# mcu.net
KiCad netlist of a schematic drawn in Altium Designer
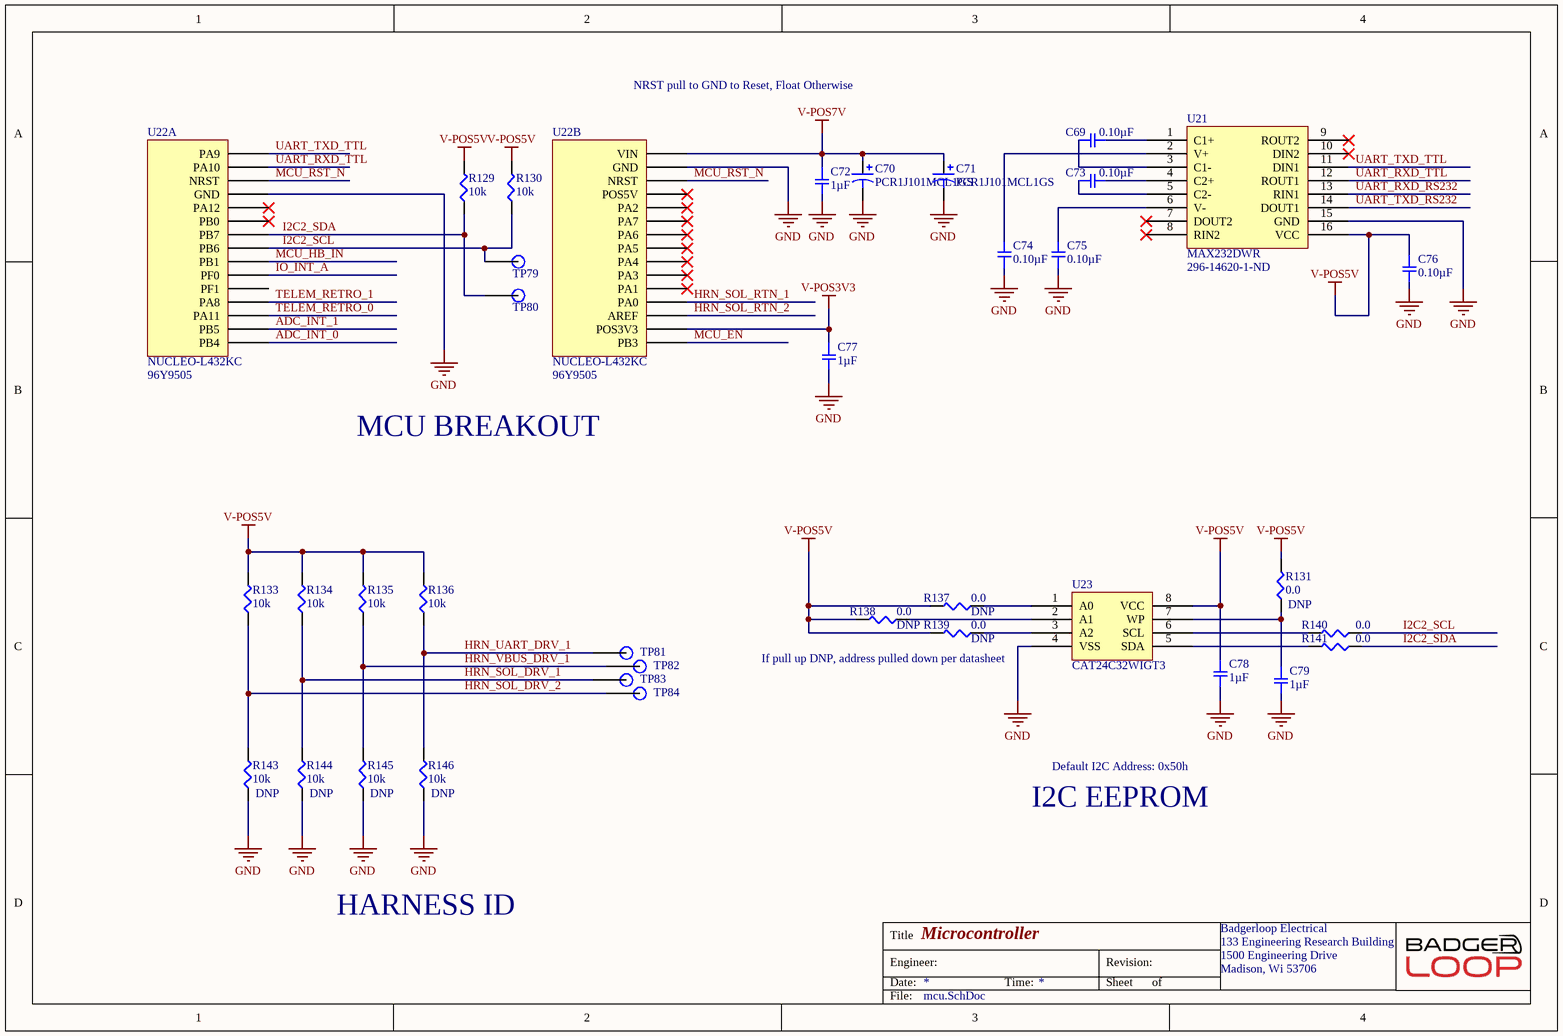
[diagram p0: mcu.SchDoc]

(export (version "E")
  (design (tool "Eeschema 10.0.6"))
  (components
    (comp (ref "C69")
      (value "0.10µF")
      (footprint "SMD-0805C")
      (description "CAP CER 0.1UF 16V X7R 0805")
      (fields
        (field (name "DIGI-KEY PART NUMBER") "490-12557-1-ND")
        (field (name "PART NUMBER") "GRM219R71C104JA01D")
      )
      (libsource (lib "capacitors") (part "GRM219R71C104JA01D"))
    )
    (comp (ref "C70")
      (value "PCR1J101MCL1GS")
      (footprint "CAPAE110103X126M")
      (description "CAP ALUM POLY 100UF 20% 63V SMD")
      (fields (field (name "MANUFACTURER") "Nichicon") (field (name "TOLERANCE") "20%"))
      (libsource (lib "capacitors") (part "PCR1J101MCL1GS"))
    )
    (comp (ref "C71")
      (value "PCR1J101MCL1GS")
      (footprint "CAPAE110103X126M")
      (description "CAP ALUM POLY 100UF 20% 63V SMD")
      (fields (field (name "MANUFACTURER") "Nichicon") (field (name "TOLERANCE") "20%"))
      (libsource (lib "capacitors") (part "PCR1J101MCL1GS"))
    )
    (comp (ref "C72")
      (value "1µF")
      (footprint "SMD-0805C")
      (description "CAP CER 1UF 50V X7R 0805")
      (fields
        (field (name "DIGI-KEY PART NUMBER") "490-4736-1-ND")
        (field (name "PART NUMBER") "GRM21BR71H105KA12L")
      )
      (libsource (lib "capacitors") (part "GRM21BR71H105KA12L"))
    )
    (comp (ref "C73")
      (value "0.10µF")
      (footprint "SMD-0805C")
      (description "CAP CER 0.1UF 16V X7R 0805")
      (fields
        (field (name "DIGI-KEY PART NUMBER") "490-12557-1-ND")
        (field (name "PART NUMBER") "GRM219R71C104JA01D")
      )
      (libsource (lib "capacitors") (part "GRM219R71C104JA01D"))
    )
    (comp (ref "C74")
      (value "0.10µF")
      (footprint "SMD-0805C")
      (description "CAP CER 0.1UF 16V X7R 0805")
      (fields
        (field (name "DIGI-KEY PART NUMBER") "490-12557-1-ND")
        (field (name "PART NUMBER") "GRM219R71C104JA01D")
      )
      (libsource (lib "capacitors") (part "GRM219R71C104JA01D"))
    )
    (comp (ref "C75")
      (value "0.10µF")
      (footprint "SMD-0805C")
      (description "CAP CER 0.1UF 16V X7R 0805")
      (fields
        (field (name "DIGI-KEY PART NUMBER") "490-12557-1-ND")
        (field (name "PART NUMBER") "GRM219R71C104JA01D")
      )
      (libsource (lib "capacitors") (part "GRM219R71C104JA01D"))
    )
    (comp (ref "C76")
      (value "0.10µF")
      (footprint "SMD-0805C")
      (description "CAP CER 0.1UF 25V X7R 0805")
      (fields
        (field (name "DIGI-KEY PART NUMBER") "490-12754-1-ND")
        (field (name "PART NUMBER") "GRM219R71E104KA01D")
      )
      (libsource (lib "capacitors") (part "GRM219R71E104KA01D"))
    )
    (comp (ref "C77")
      (value "1µF")
      (footprint "SMD-0805C")
      (description "CAP CER 1UF 50V X7R 0805")
      (fields
        (field (name "DIGI-KEY PART NUMBER") "490-4736-1-ND")
        (field (name "PART NUMBER") "GRM21BR71H105KA12L")
      )
      (libsource (lib "capacitors") (part "GRM21BR71H105KA12L"))
    )
    (comp (ref "C78")
      (value "1µF")
      (footprint "SMD-0805C")
      (description "CAP CER 1UF 50V X7R 0805")
      (fields
        (field (name "DIGI-KEY PART NUMBER") "490-4736-1-ND")
        (field (name "PART NUMBER") "GRM21BR71H105KA12L")
      )
      (libsource (lib "capacitors") (part "GRM21BR71H105KA12L"))
    )
    (comp (ref "C79")
      (value "1µF")
      (footprint "SMD-0805C")
      (description "CAP CER 1UF 50V X7R 0805")
      (fields
        (field (name "DIGI-KEY PART NUMBER") "490-4736-1-ND")
        (field (name "PART NUMBER") "GRM21BR71H105KA12L")
      )
      (libsource (lib "capacitors") (part "GRM21BR71H105KA12L"))
    )
    (comp (ref "R129")
      (value "10k")
      (footprint "SMD-0805-RES")
      (description "RES SMD 10K OHM 5% 1/2W 0805")
      (fields (field (name "PART NUMBER") "ERJ-P06J103V") (field (name "DIGI-KEY PART NUMBER") "P10KADCT-ND"))
      (libsource (lib "resistors") (part "ERJ-P06J103V"))
    )
    (comp (ref "R130")
      (value "10k")
      (footprint "SMD-0805-RES")
      (description "RES SMD 10K OHM 5% 1/2W 0805")
      (fields (field (name "PART NUMBER") "ERJ-P06J103V") (field (name "DIGI-KEY PART NUMBER") "P10KADCT-ND"))
      (libsource (lib "resistors") (part "ERJ-P06J103V"))
    )
    (comp (ref "R131")
      (value "0.0")
      (footprint "SMD-0805-RES")
      (description "RES SMD 0.0 OHM JUMPER 1/8W 0805")
      (fields
        (field (name "PART NUMBER") "ERJ-6GEY0R00V")
        (field (name "DIGI-KEY PART NUMBER") "P0.0ACT-ND")
        (field (name "DNP") "DNP")
      )
      (libsource (lib "resistors") (part "ERJ-6GEY0R00V"))
    )
    (comp (ref "R133")
      (value "10k")
      (footprint "SMD-0805-RES")
      (description "RES SMD 10K OHM 5% 1/2W 0805")
      (fields (field (name "PART NUMBER") "ERJ-P06J103V") (field (name "DIGI-KEY PART NUMBER") "P10KADCT-ND"))
      (libsource (lib "resistors") (part "ERJ-P06J103V"))
    )
    (comp (ref "R134")
      (value "10k")
      (footprint "SMD-0805-RES")
      (description "RES SMD 10K OHM 5% 1/2W 0805")
      (fields (field (name "PART NUMBER") "ERJ-P06J103V") (field (name "DIGI-KEY PART NUMBER") "P10KADCT-ND"))
      (libsource (lib "resistors") (part "ERJ-P06J103V"))
    )
    (comp (ref "R135")
      (value "10k")
      (footprint "SMD-0805-RES")
      (description "RES SMD 10K OHM 5% 1/2W 0805")
      (fields (field (name "PART NUMBER") "ERJ-P06J103V") (field (name "DIGI-KEY PART NUMBER") "P10KADCT-ND"))
      (libsource (lib "resistors") (part "ERJ-P06J103V"))
    )
    (comp (ref "R136")
      (value "10k")
      (footprint "SMD-0805-RES")
      (description "RES SMD 10K OHM 5% 1/2W 0805")
      (fields (field (name "PART NUMBER") "ERJ-P06J103V") (field (name "DIGI-KEY PART NUMBER") "P10KADCT-ND"))
      (libsource (lib "resistors") (part "ERJ-P06J103V"))
    )
    (comp (ref "R137")
      (value "0.0")
      (footprint "SMD-0805-RES")
      (description "RES SMD 0.0 OHM JUMPER 1/8W 0805")
      (fields
        (field (name "PART NUMBER") "ERJ-6GEY0R00V")
        (field (name "DIGI-KEY PART NUMBER") "P0.0ACT-ND")
        (field (name "DNP") "DNP")
      )
      (libsource (lib "resistors") (part "ERJ-6GEY0R00V"))
    )
    (comp (ref "R138")
      (value "0.0")
      (footprint "SMD-0805-RES")
      (description "RES SMD 0.0 OHM JUMPER 1/8W 0805")
      (fields
        (field (name "PART NUMBER") "ERJ-6GEY0R00V")
        (field (name "DIGI-KEY PART NUMBER") "P0.0ACT-ND")
        (field (name "DNP") "DNP")
      )
      (libsource (lib "resistors") (part "ERJ-6GEY0R00V"))
    )
    (comp (ref "R139")
      (value "0.0")
      (footprint "SMD-0805-RES")
      (description "RES SMD 0.0 OHM JUMPER 1/8W 0805")
      (fields
        (field (name "PART NUMBER") "ERJ-6GEY0R00V")
        (field (name "DIGI-KEY PART NUMBER") "P0.0ACT-ND")
        (field (name "DNP") "DNP")
      )
      (libsource (lib "resistors") (part "ERJ-6GEY0R00V"))
    )
    (comp (ref "R140")
      (value "0.0")
      (footprint "SMD-0805-RES")
      (description "RES SMD 0.0 OHM JUMPER 1/8W 0805")
      (fields (field (name "PART NUMBER") "ERJ-6GEY0R00V") (field (name "DIGI-KEY PART NUMBER") "P0.0ACT-ND"))
      (libsource (lib "resistors") (part "ERJ-6GEY0R00V"))
    )
    (comp (ref "R141")
      (value "0.0")
      (footprint "SMD-0805-RES")
      (description "RES SMD 0.0 OHM JUMPER 1/8W 0805")
      (fields (field (name "PART NUMBER") "ERJ-6GEY0R00V") (field (name "DIGI-KEY PART NUMBER") "P0.0ACT-ND"))
      (libsource (lib "resistors") (part "ERJ-6GEY0R00V"))
    )
    (comp (ref "R143")
      (value "10k")
      (footprint "SMD-0805-RES")
      (description "RES SMD 10K OHM 5% 1/2W 0805")
      (fields
        (field (name "PART NUMBER") "ERJ-P06J103V")
        (field (name "DIGI-KEY PART NUMBER") "P10KADCT-ND")
        (field (name "DNP") "DNP")
      )
      (libsource (lib "resistors") (part "ERJ-P06J103V"))
    )
    (comp (ref "R144")
      (value "10k")
      (footprint "SMD-0805-RES")
      (description "RES SMD 10K OHM 5% 1/2W 0805")
      (fields
        (field (name "PART NUMBER") "ERJ-P06J103V")
        (field (name "DIGI-KEY PART NUMBER") "P10KADCT-ND")
        (field (name "DNP") "DNP")
      )
      (libsource (lib "resistors") (part "ERJ-P06J103V"))
    )
    (comp (ref "R145")
      (value "10k")
      (footprint "SMD-0805-RES")
      (description "RES SMD 10K OHM 5% 1/2W 0805")
      (fields
        (field (name "PART NUMBER") "ERJ-P06J103V")
        (field (name "DIGI-KEY PART NUMBER") "P10KADCT-ND")
        (field (name "DNP") "DNP")
      )
      (libsource (lib "resistors") (part "ERJ-P06J103V"))
    )
    (comp (ref "R146")
      (value "10k")
      (footprint "SMD-0805-RES")
      (description "RES SMD 10K OHM 5% 1/2W 0805")
      (fields
        (field (name "PART NUMBER") "ERJ-P06J103V")
        (field (name "DIGI-KEY PART NUMBER") "P10KADCT-ND")
        (field (name "DNP") "DNP")
      )
      (libsource (lib "resistors") (part "ERJ-P06J103V"))
    )
    (comp (ref "TP79")
      (value "TP")
      (footprint "Test Point")
      (description "SMD TEST POINT")
      (libsource (lib "misc") (part "TP"))
    )
    (comp (ref "TP80")
      (value "TP")
      (footprint "Test Point")
      (description "SMD TEST POINT")
      (libsource (lib "misc") (part "TP"))
    )
    (comp (ref "TP81")
      (value "TP")
      (footprint "Test Point")
      (description "SMD TEST POINT")
      (libsource (lib "misc") (part "TP"))
    )
    (comp (ref "TP82")
      (value "TP")
      (footprint "Test Point")
      (description "SMD TEST POINT")
      (libsource (lib "misc") (part "TP"))
    )
    (comp (ref "TP83")
      (value "TP")
      (footprint "Test Point")
      (description "SMD TEST POINT")
      (libsource (lib "misc") (part "TP"))
    )
    (comp (ref "TP84")
      (value "TP")
      (footprint "Test Point")
      (description "SMD TEST POINT")
      (libsource (lib "misc") (part "TP"))
    )
    (comp (ref "U21")
      (value "MAX232DWR")
      (footprint "SOP127P1060X175-16N")
      (description "IC DRVR/RCVR MULTCH RS232 16SOIC")
      (fields
        (field (name "MANUFACTURER") "Texas Instruments")
        (field (name "SUPPLIER PART NUMBER 1") "296-14620-1-ND")
      )
      (libsource (lib "ic") (part "MAX232DWR"))
    )
    (comp (ref "U22")
      (value "NUCLEO-L432KC")
      (footprint "NUCLEO-L432KC")
      (description "BOARD NUCLEO STM32F303K8T6")
      (fields
        (field (name "MANUFACTURER") "STMicroelectronics")
        (field (name "SUPPLIER PART NUMBER 2") "96Y9505")
      )
      (libsource (lib "ic") (part "NUCLEO-L432KC"))
    )
    (comp (ref "U23")
      (value "CAT24C32WIGT3")
      (footprint "SOP127P600X175-8N")
      (description "IC EEPROM 32K I2C 1MHZ 8SOIC")
      (fields (field (name "MANUFACTURER") "ON Semiconductor"))
      (libsource (lib "ic") (part "CAT24C32WIGT3"))
    )
  )
  (nets
    (net (code "1") (name "/ADC_INT_0") (class "Default")
      (node (ref "U22") (pin "3.15") (pinfunction "PB4_3.15") (pintype "passive"))
    )
    (net (code "2") (name "/ADC_INT_1") (class "Default")
      (node (ref "U22") (pin "3.14") (pinfunction "PB5_3.14") (pintype "passive"))
    )
    (net (code "3") (name "/HRN_SOL_DRV_1") (class "Default")
      (node (ref "R134") (pin "1") (pinfunction "1_1") (pintype "passive"))
      (node (ref "R144") (pin "2") (pinfunction "2_2") (pintype "passive"))
      (node (ref "TP83") (pin "1") (pinfunction "1_1") (pintype "passive"))
    )
    (net (code "4") (name "/HRN_SOL_DRV_2") (class "Default")
      (node (ref "R133") (pin "1") (pinfunction "1_1") (pintype "passive"))
      (node (ref "R143") (pin "2") (pinfunction "2_2") (pintype "passive"))
      (node (ref "TP84") (pin "1") (pinfunction "1_1") (pintype "passive"))
    )
    (net (code "5") (name "/HRN_SOL_RTN_1") (class "Default")
      (node (ref "U22") (pin "4.12") (pinfunction "PA0_4.12") (pintype "passive"))
    )
    (net (code "6") (name "/HRN_SOL_RTN_2") (class "Default")
      (node (ref "U22") (pin "4.13") (pinfunction "AREF_4.13") (pintype "passive"))
    )
    (net (code "7") (name "/HRN_UART_DRV_1") (class "Default")
      (node (ref "R136") (pin "1") (pinfunction "1_1") (pintype "passive"))
      (node (ref "R146") (pin "2") (pinfunction "2_2") (pintype "passive"))
      (node (ref "TP81") (pin "1") (pinfunction "1_1") (pintype "passive"))
    )
    (net (code "8") (name "/HRN_VBUS_DRV_1") (class "Default")
      (node (ref "R135") (pin "1") (pinfunction "1_1") (pintype "passive"))
      (node (ref "R145") (pin "2") (pinfunction "2_2") (pintype "passive"))
      (node (ref "TP82") (pin "1") (pinfunction "1_1") (pintype "passive"))
    )
    (net (code "9") (name "/I2C2_SCL") (class "Default")
      (node (ref "R130") (pin "1") (pinfunction "1_1") (pintype "passive"))
      (node (ref "R140") (pin "1") (pinfunction "1_1") (pintype "passive"))
      (node (ref "TP79") (pin "1") (pinfunction "1_1") (pintype "passive"))
      (node (ref "U22") (pin "3.8") (pinfunction "PB6_3.8") (pintype "passive"))
    )
    (net (code "10") (name "/I2C2_SDA") (class "Default")
      (node (ref "R129") (pin "1") (pinfunction "1_1") (pintype "passive"))
      (node (ref "R141") (pin "1") (pinfunction "1_1") (pintype "passive"))
      (node (ref "TP80") (pin "1") (pinfunction "1_1") (pintype "passive"))
      (node (ref "U22") (pin "3.7") (pinfunction "PB7_3.7") (pintype "passive"))
    )
    (net (code "11") (name "/IO_INT_A") (class "Default")
      (node (ref "U22") (pin "3.10") (pinfunction "PF0_3.10") (pintype "passive"))
    )
    (net (code "12") (name "/MCU_EN") (class "Default")
      (node (ref "U22") (pin "4.15") (pinfunction "PB3_4.15") (pintype "passive"))
    )
    (net (code "13") (name "/MCU_HB_IN") (class "Default")
      (node (ref "U22") (pin "3.9") (pinfunction "PB1_3.9") (pintype "passive"))
    )
    (net (code "14") (name "/MCU_RST_N") (class "Default")
      (node (ref "U22") (pin "3.3") (pinfunction "NRST_3.3") (pintype "passive"))
      (node (ref "U22") (pin "4.3") (pinfunction "NRST_4.3") (pintype "passive"))
    )
    (net (code "15") (name "/TELEM_RETRO_0") (class "Default")
      (node (ref "U22") (pin "3.13") (pinfunction "PA11_3.13") (pintype "passive"))
    )
    (net (code "16") (name "/TELEM_RETRO_1") (class "Default")
      (node (ref "U22") (pin "3.12") (pinfunction "PA8_3.12") (pintype "passive"))
    )
    (net (code "17") (name "/UART_RXD_RS232") (class "Default")
      (node (ref "U21") (pin "13") (pinfunction "RIN1_13") (pintype "passive"))
    )
    (net (code "18") (name "/UART_RXD_TTL") (class "Default")
      (node (ref "U21") (pin "12") (pinfunction "ROUT1_12") (pintype "passive"))
      (node (ref "U22") (pin "3.2") (pinfunction "PA10_3.2") (pintype "passive"))
    )
    (net (code "19") (name "/UART_TXD_RS232") (class "Default")
      (node (ref "U21") (pin "14") (pinfunction "DOUT1_14") (pintype "passive"))
    )
    (net (code "20") (name "/UART_TXD_TTL") (class "Default")
      (node (ref "U21") (pin "11") (pinfunction "DIN1_11") (pintype "passive"))
      (node (ref "U22") (pin "3.1") (pinfunction "PA9_3.1") (pintype "passive"))
    )
    (net (code "21") (name "GND") (class "Default")
      (node (ref "C70") (pin "2") (pinfunction "2_2") (pintype "passive"))
      (node (ref "C71") (pin "2") (pinfunction "2_2") (pintype "passive"))
      (node (ref "C72") (pin "2") (pinfunction "2_2") (pintype "passive"))
      (node (ref "C74") (pin "1") (pinfunction "1_1") (pintype "passive"))
      (node (ref "C75") (pin "1") (pinfunction "1_1") (pintype "passive"))
      (node (ref "C76") (pin "2") (pinfunction "2_2") (pintype "passive"))
      (node (ref "C77") (pin "2") (pinfunction "2_2") (pintype "passive"))
      (node (ref "C78") (pin "2") (pinfunction "2_2") (pintype "passive"))
      (node (ref "C79") (pin "2") (pinfunction "2_2") (pintype "passive"))
      (node (ref "R143") (pin "1") (pinfunction "1_1") (pintype "passive"))
      (node (ref "R144") (pin "1") (pinfunction "1_1") (pintype "passive"))
      (node (ref "R145") (pin "1") (pinfunction "1_1") (pintype "passive"))
      (node (ref "R146") (pin "1") (pinfunction "1_1") (pintype "passive"))
      (node (ref "U21") (pin "15") (pinfunction "GND_15") (pintype "passive"))
      (node (ref "U22") (pin "3.4") (pinfunction "GND_3.4") (pintype "passive"))
      (node (ref "U22") (pin "4.2") (pinfunction "GND_4.2") (pintype "passive"))
      (node (ref "U23") (pin "4") (pinfunction "VSS_4") (pintype "passive"))
    )
    (net (code "22") (name "Net-(U21-C1+)") (class "Default")
      (node (ref "C69") (pin "2") (pinfunction "2_2") (pintype "passive"))
      (node (ref "U21") (pin "1") (pinfunction "C1+_1") (pintype "passive"))
    )
    (net (code "23") (name "Net-(U21-C1-)") (class "Default")
      (node (ref "C69") (pin "1") (pinfunction "1_1") (pintype "passive"))
      (node (ref "U21") (pin "3") (pinfunction "C1-_3") (pintype "passive"))
    )
    (net (code "24") (name "Net-(U21-C2+)") (class "Default")
      (node (ref "C73") (pin "2") (pinfunction "2_2") (pintype "passive"))
      (node (ref "U21") (pin "4") (pinfunction "C2+_4") (pintype "passive"))
    )
    (net (code "25") (name "Net-(U21-C2-)") (class "Default")
      (node (ref "C73") (pin "1") (pinfunction "1_1") (pintype "passive"))
      (node (ref "U21") (pin "5") (pinfunction "C2-_5") (pintype "passive"))
    )
    (net (code "26") (name "Net-(U21-V+)") (class "Default")
      (node (ref "C74") (pin "2") (pinfunction "2_2") (pintype "passive"))
      (node (ref "U21") (pin "2") (pinfunction "V+_2") (pintype "passive"))
    )
    (net (code "27") (name "Net-(U21-V-)") (class "Default")
      (node (ref "C75") (pin "2") (pinfunction "2_2") (pintype "passive"))
      (node (ref "U21") (pin "6") (pinfunction "V-_6") (pintype "passive"))
    )
    (net (code "28") (name "Net-(U23-A0)") (class "Default")
      (node (ref "R137") (pin "1") (pinfunction "1_1") (pintype "passive"))
      (node (ref "U23") (pin "1") (pinfunction "A0_1") (pintype "passive"))
    )
    (net (code "29") (name "Net-(U23-A1)") (class "Default")
      (node (ref "R138") (pin "1") (pinfunction "1_1") (pintype "passive"))
      (node (ref "U23") (pin "2") (pinfunction "A1_2") (pintype "passive"))
    )
    (net (code "30") (name "Net-(U23-A2)") (class "Default")
      (node (ref "R139") (pin "1") (pinfunction "1_1") (pintype "passive"))
      (node (ref "U23") (pin "3") (pinfunction "A2_3") (pintype "passive"))
    )
    (net (code "31") (name "Net-(U23-SCL)") (class "Default")
      (node (ref "R140") (pin "2") (pinfunction "2_2") (pintype "passive"))
      (node (ref "U23") (pin "6") (pinfunction "SCL_6") (pintype "passive"))
    )
    (net (code "32") (name "Net-(U23-SDA)") (class "Default")
      (node (ref "R141") (pin "2") (pinfunction "2_2") (pintype "passive"))
      (node (ref "U23") (pin "5") (pinfunction "SDA_5") (pintype "passive"))
    )
    (net (code "33") (name "Net-(U23-WP)") (class "Default")
      (node (ref "C79") (pin "1") (pinfunction "1_1") (pintype "passive"))
      (node (ref "R131") (pin "1") (pinfunction "1_1") (pintype "passive"))
      (node (ref "U23") (pin "7") (pinfunction "WP_7") (pintype "passive"))
    )
    (net (code "34") (name "V-POS3V3") (class "Default")
      (node (ref "C77") (pin "1") (pinfunction "1_1") (pintype "passive"))
      (node (ref "U22") (pin "4.14") (pinfunction "POS3V3_4.14") (pintype "passive"))
    )
    (net (code "35") (name "V-POS5V") (class "Default")
      (node (ref "C76") (pin "1") (pinfunction "1_1") (pintype "passive"))
      (node (ref "C78") (pin "1") (pinfunction "1_1") (pintype "passive"))
      (node (ref "R129") (pin "2") (pinfunction "2_2") (pintype "passive"))
      (node (ref "R130") (pin "2") (pinfunction "2_2") (pintype "passive"))
      (node (ref "R131") (pin "2") (pinfunction "2_2") (pintype "passive"))
      (node (ref "R133") (pin "2") (pinfunction "2_2") (pintype "passive"))
      (node (ref "R134") (pin "2") (pinfunction "2_2") (pintype "passive"))
      (node (ref "R135") (pin "2") (pinfunction "2_2") (pintype "passive"))
      (node (ref "R136") (pin "2") (pinfunction "2_2") (pintype "passive"))
      (node (ref "R137") (pin "2") (pinfunction "2_2") (pintype "passive"))
      (node (ref "R138") (pin "2") (pinfunction "2_2") (pintype "passive"))
      (node (ref "R139") (pin "2") (pinfunction "2_2") (pintype "passive"))
      (node (ref "U21") (pin "16") (pinfunction "VCC_16") (pintype "passive"))
      (node (ref "U23") (pin "8") (pinfunction "VCC_8") (pintype "passive"))
    )
    (net (code "36") (name "V-POS7V") (class "Default")
      (node (ref "C70") (pin "1") (pinfunction "1_1") (pintype "passive"))
      (node (ref "C71") (pin "1") (pinfunction "1_1") (pintype "passive"))
      (node (ref "C72") (pin "1") (pinfunction "1_1") (pintype "passive"))
      (node (ref "U22") (pin "4.1") (pinfunction "VIN_4.1") (pintype "passive"))
    )
    (net (code "37") (name "unconnected-(U21-DIN2-Pad10)") (class "Default")
      (node (ref "U21") (pin "10") (pinfunction "DIN2_10") (pintype "passive+no_connect"))
    )
    (net (code "38") (name "unconnected-(U21-DOUT2-Pad7)") (class "Default")
      (node (ref "U21") (pin "7") (pinfunction "DOUT2_7") (pintype "passive+no_connect"))
    )
    (net (code "39") (name "unconnected-(U21-RIN2-Pad8)") (class "Default")
      (node (ref "U21") (pin "8") (pinfunction "RIN2_8") (pintype "passive+no_connect"))
    )
    (net (code "40") (name "unconnected-(U21-ROUT2-Pad9)") (class "Default")
      (node (ref "U21") (pin "9") (pinfunction "ROUT2_9") (pintype "passive+no_connect"))
    )
    (net (code "41") (name "unconnected-(U22A-PA12-Pad3.5)") (class "Default")
      (node (ref "U22") (pin "3.5") (pinfunction "PA12_3.5") (pintype "passive+no_connect"))
    )
    (net (code "42") (name "unconnected-(U22A-PB0-Pad3.6)") (class "Default")
      (node (ref "U22") (pin "3.6") (pinfunction "PB0_3.6") (pintype "passive+no_connect"))
    )
    (net (code "43") (name "unconnected-(U22A-PF1-Pad3.11)") (class "Default")
      (node (ref "U22") (pin "3.11") (pinfunction "PF1_3.11") (pintype "passive"))
    )
    (net (code "44") (name "unconnected-(U22B-PA1-Pad4.11)") (class "Default")
      (node (ref "U22") (pin "4.11") (pinfunction "PA1_4.11") (pintype "passive+no_connect"))
    )
    (net (code "45") (name "unconnected-(U22B-PA2-Pad4.5)") (class "Default")
      (node (ref "U22") (pin "4.5") (pinfunction "PA2_4.5") (pintype "passive+no_connect"))
    )
    (net (code "46") (name "unconnected-(U22B-PA3-Pad4.10)") (class "Default")
      (node (ref "U22") (pin "4.10") (pinfunction "PA3_4.10") (pintype "passive+no_connect"))
    )
    (net (code "47") (name "unconnected-(U22B-PA4-Pad4.9)") (class "Default")
      (node (ref "U22") (pin "4.9") (pinfunction "PA4_4.9") (pintype "passive+no_connect"))
    )
    (net (code "48") (name "unconnected-(U22B-PA5-Pad4.8)") (class "Default")
      (node (ref "U22") (pin "4.8") (pinfunction "PA5_4.8") (pintype "passive+no_connect"))
    )
    (net (code "49") (name "unconnected-(U22B-PA6-Pad4.7)") (class "Default")
      (node (ref "U22") (pin "4.7") (pinfunction "PA6_4.7") (pintype "passive+no_connect"))
    )
    (net (code "50") (name "unconnected-(U22B-PA7-Pad4.6)") (class "Default")
      (node (ref "U22") (pin "4.6") (pinfunction "PA7_4.6") (pintype "passive+no_connect"))
    )
    (net (code "51") (name "unconnected-(U22B-POS5V-Pad4.4)") (class "Default")
      (node (ref "U22") (pin "4.4") (pinfunction "POS5V_4.4") (pintype "passive+no_connect"))
    )
  )
)
